# ICs.net
KiCad netlist of a schematic drawn in Altium Designer
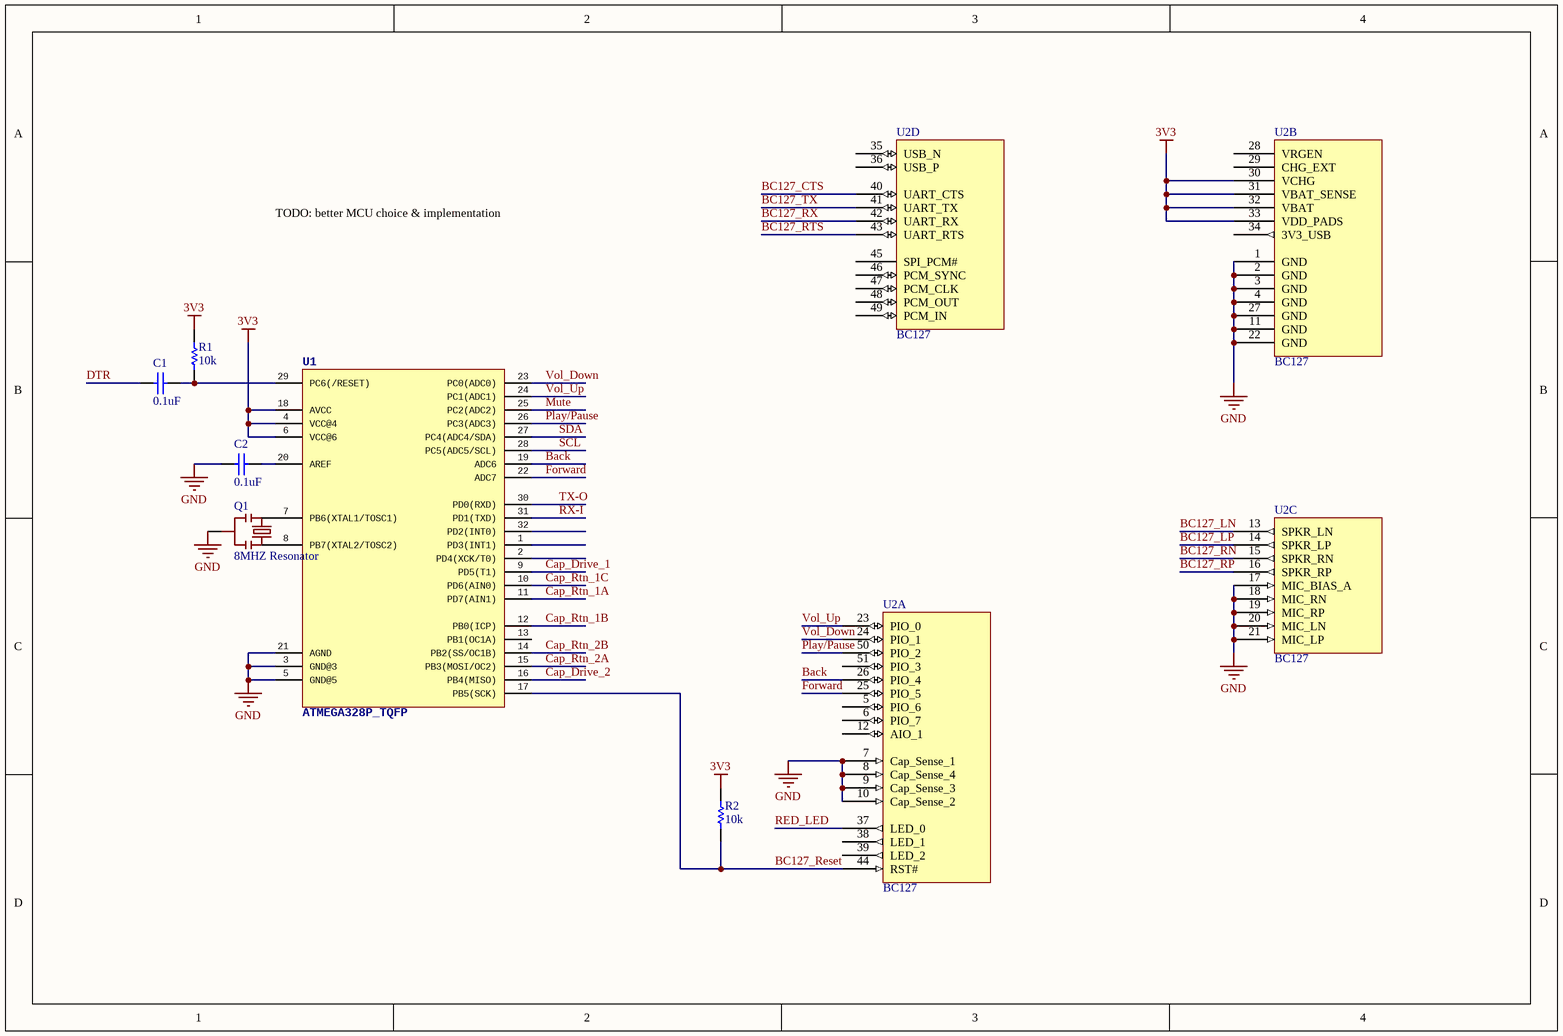
[diagram p0: ICs.SchDoc]

(export (version "E")
  (design (tool "Eeschema 10.0.6"))
  (components
    (comp (ref "C1")
      (value "0.1uF")
      (footprint "CAPC1608X09N")
      (fields
        (field (name "DIGIKEY PART NUMBER") "490-3285-1-ND")
        (field (name "VOLTAGE") "100V")
        (field (name "TOLERANCE") "10%")
      )
      (libsource (lib "Speaker Library") (part "CAP CER 0.1uF 0603"))
    )
    (comp (ref "C2")
      (value "0.1uF")
      (footprint "CAPC1608X09N")
      (fields
        (field (name "DIGIKEY PART NUMBER") "490-3285-1-ND")
        (field (name "VOLTAGE") "100V")
        (field (name "TOLERANCE") "10%")
      )
      (libsource (lib "Speaker Library") (part "CAP CER 0.1uF 0603"))
    )
    (comp (ref "Q1")
      (value "8MHZ Resonator")
      (footprint "MURATA CSTCE8M00G52Z-R0")
      (fields (field (name "DIGIKEY PART NUMBER") "490-5995-1-ND"))
      (libsource (lib "Speaker Library") (part "RESONATOR 8MHZ"))
    )
    (comp (ref "R1")
      (value "10k")
      (footprint "RESC1608X06N")
      (fields
        (field (name "TOLERANCE") "1%")
        (field (name "POWER") "0.1W")
        (field (name "MANUFACTURER") "Yageo")
      )
      (libsource (lib "Speaker Library") (part "RES 10K 0603"))
    )
    (comp (ref "R2")
      (value "10k")
      (footprint "RESC1608X06N")
      (fields
        (field (name "TOLERANCE") "1%")
        (field (name "POWER") "0.1W")
        (field (name "MANUFACTURER") "Yageo")
      )
      (libsource (lib "Speaker Library") (part "RES 10K 0603"))
    )
    (comp (ref "U1")
      (value "ATMEGA328P_TQFP")
      (footprint "TQFP32-08")
      (fields (field (name "DIGIKEY PART NUMBER") "ATMEGA328P-AURCT-ND"))
      (libsource (lib "Speaker Library") (part "ATMEGA328P_TQFP"))
    )
    (comp (ref "U2") (value "BC127") (footprint "BC127 - No Keepout") (libsource (lib "") (part "BC127_1")))
  )
  (nets
    (net (code "1") (name "/BC127_CTS") (class "Default")
      (node (ref "U2") (pin "40") (pinfunction "UART_CTS_40") (pintype "bidirectional"))
    )
    (net (code "2") (name "/BC127_LN") (class "Default")
      (node (ref "U2") (pin "13") (pinfunction "SPKR_LN_13") (pintype "output"))
    )
    (net (code "3") (name "/BC127_LP") (class "Default")
      (node (ref "U2") (pin "14") (pinfunction "SPKR_LP_14") (pintype "output"))
    )
    (net (code "4") (name "/BC127_RN") (class "Default")
      (node (ref "U2") (pin "15") (pinfunction "SPKR_RN_15") (pintype "output"))
    )
    (net (code "5") (name "/BC127_RP") (class "Default")
      (node (ref "U2") (pin "16") (pinfunction "SPKR_RP_16") (pintype "output"))
    )
    (net (code "6") (name "/BC127_RTS") (class "Default")
      (node (ref "U2") (pin "43") (pinfunction "UART_RTS_43") (pintype "bidirectional"))
    )
    (net (code "7") (name "/BC127_RX") (class "Default")
      (node (ref "U2") (pin "42") (pinfunction "UART_RX_42") (pintype "bidirectional"))
    )
    (net (code "8") (name "/BC127_Reset") (class "Default")
      (node (ref "R2") (pin "1") (pinfunction "1_1") (pintype "passive"))
      (node (ref "U1") (pin "17") (pinfunction "PB5(SCK)_17") (pintype "passive"))
      (node (ref "U2") (pin "44") (pinfunction "RST#_44") (pintype "input"))
    )
    (net (code "9") (name "/BC127_TX") (class "Default")
      (node (ref "U2") (pin "41") (pinfunction "UART_TX_41") (pintype "bidirectional"))
    )
    (net (code "10") (name "/Back") (class "Default")
      (node (ref "U1") (pin "19") (pinfunction "ADC6_19") (pintype "passive"))
      (node (ref "U2") (pin "26") (pinfunction "PIO_4_26") (pintype "bidirectional"))
    )
    (net (code "11") (name "/Cap_Drive_1") (class "Default")
      (node (ref "U1") (pin "9") (pinfunction "PD5(T1)_9") (pintype "passive"))
    )
    (net (code "12") (name "/Cap_Drive_2") (class "Default")
      (node (ref "U1") (pin "16") (pinfunction "PB4(MISO)_16") (pintype "passive"))
    )
    (net (code "13") (name "/Cap_Rtn_1A") (class "Default")
      (node (ref "U1") (pin "11") (pinfunction "PD7(AIN1)_11") (pintype "passive"))
    )
    (net (code "14") (name "/Cap_Rtn_1B") (class "Default")
      (node (ref "U1") (pin "12") (pinfunction "PB0(ICP)_12") (pintype "passive"))
    )
    (net (code "15") (name "/Cap_Rtn_1C") (class "Default")
      (node (ref "U1") (pin "10") (pinfunction "PD6(AIN0)_10") (pintype "passive"))
    )
    (net (code "16") (name "/Cap_Rtn_2A") (class "Default")
      (node (ref "U1") (pin "15") (pinfunction "PB3(MOSI/OC2)_15") (pintype "passive"))
    )
    (net (code "17") (name "/Cap_Rtn_2B") (class "Default")
      (node (ref "U1") (pin "14") (pinfunction "PB2(SS/OC1B)_14") (pintype "passive"))
    )
    (net (code "18") (name "/DTR") (class "Default")
      (node (ref "C1") (pin "1") (pinfunction "1_1") (pintype "passive"))
    )
    (net (code "19") (name "/Forward") (class "Default")
      (node (ref "U1") (pin "22") (pinfunction "ADC7_22") (pintype "passive"))
      (node (ref "U2") (pin "25") (pinfunction "PIO_5_25") (pintype "bidirectional"))
    )
    (net (code "20") (name "/Mute") (class "Default")
      (node (ref "U1") (pin "25") (pinfunction "PC2(ADC2)_25") (pintype "passive"))
    )
    (net (code "21") (name "/Play{slash}Pause") (class "Default")
      (node (ref "U1") (pin "26") (pinfunction "PC3(ADC3)_26") (pintype "passive"))
      (node (ref "U2") (pin "50") (pinfunction "PIO_2_50") (pintype "bidirectional"))
    )
    (net (code "22") (name "/RED_LED") (class "Default")
      (node (ref "U2") (pin "37") (pinfunction "LED_0_37") (pintype "output"))
    )
    (net (code "23") (name "/RX-I") (class "Default")
      (node (ref "U1") (pin "31") (pinfunction "PD1(TXD)_31") (pintype "passive"))
    )
    (net (code "24") (name "/SCL") (class "Default")
      (node (ref "U1") (pin "28") (pinfunction "PC5(ADC5/SCL)_28") (pintype "passive"))
    )
    (net (code "25") (name "/SDA") (class "Default")
      (node (ref "U1") (pin "27") (pinfunction "PC4(ADC4/SDA)_27") (pintype "passive"))
    )
    (net (code "26") (name "/TX-O") (class "Default")
      (node (ref "U1") (pin "30") (pinfunction "PD0(RXD)_30") (pintype "passive"))
    )
    (net (code "27") (name "/Vol_Down") (class "Default")
      (node (ref "U1") (pin "23") (pinfunction "PC0(ADC0)_23") (pintype "passive"))
      (node (ref "U2") (pin "24") (pinfunction "PIO_1_24") (pintype "bidirectional"))
    )
    (net (code "28") (name "/Vol_Up") (class "Default")
      (node (ref "U1") (pin "24") (pinfunction "PC1(ADC1)_24") (pintype "passive"))
      (node (ref "U2") (pin "23") (pinfunction "PIO_0_23") (pintype "bidirectional"))
    )
    (net (code "29") (name "3V3") (class "Default")
      (node (ref "R1") (pin "2") (pinfunction "2_2") (pintype "passive"))
      (node (ref "R2") (pin "2") (pinfunction "2_2") (pintype "passive"))
      (node (ref "U1") (pin "18") (pinfunction "AVCC_18") (pintype "passive"))
      (node (ref "U1") (pin "4") (pinfunction "VCC@4_4") (pintype "power_in"))
      (node (ref "U1") (pin "6") (pinfunction "VCC@6_6") (pintype "power_in"))
      (node (ref "U2") (pin "30") (pinfunction "VCHG_30") (pintype "passive"))
      (node (ref "U2") (pin "31") (pinfunction "VBAT_SENSE_31") (pintype "passive"))
      (node (ref "U2") (pin "32") (pinfunction "VBAT_32") (pintype "passive"))
      (node (ref "U2") (pin "33") (pinfunction "VDD_PADS_33") (pintype "power_in"))
    )
    (net (code "30") (name "GND") (class "Default")
      (node (ref "C2") (pin "1") (pinfunction "1_1") (pintype "passive"))
      (node (ref "Q1") (pin "2") (pinfunction "GND_2") (pintype "passive"))
      (node (ref "U1") (pin "21") (pinfunction "AGND_21") (pintype "power_in"))
      (node (ref "U1") (pin "3") (pinfunction "GND@3_3") (pintype "power_in"))
      (node (ref "U1") (pin "5") (pinfunction "GND@5_5") (pintype "power_in"))
      (node (ref "U2") (pin "1") (pinfunction "GND_1") (pintype "power_in"))
      (node (ref "U2") (pin "10") (pinfunction "Cap_Sense_2_10") (pintype "input"))
      (node (ref "U2") (pin "11") (pinfunction "GND_11") (pintype "power_in"))
      (node (ref "U2") (pin "17") (pinfunction "MIC_BIAS_A_17") (pintype "input"))
      (node (ref "U2") (pin "18") (pinfunction "MIC_RN_18") (pintype "input"))
      (node (ref "U2") (pin "19") (pinfunction "MIC_RP_19") (pintype "input"))
      (node (ref "U2") (pin "2") (pinfunction "GND_2") (pintype "power_in"))
      (node (ref "U2") (pin "20") (pinfunction "MIC_LN_20") (pintype "input"))
      (node (ref "U2") (pin "21") (pinfunction "MIC_LP_21") (pintype "input"))
      (node (ref "U2") (pin "22") (pinfunction "GND_22") (pintype "power_in"))
      (node (ref "U2") (pin "27") (pinfunction "GND_27") (pintype "power_in"))
      (node (ref "U2") (pin "3") (pinfunction "GND_3") (pintype "power_in"))
      (node (ref "U2") (pin "4") (pinfunction "GND_4") (pintype "power_in"))
      (node (ref "U2") (pin "7") (pinfunction "Cap_Sense_1_7") (pintype "input"))
      (node (ref "U2") (pin "8") (pinfunction "Cap_Sense_4_8") (pintype "input"))
      (node (ref "U2") (pin "9") (pinfunction "Cap_Sense_3_9") (pintype "input"))
    )
    (net (code "31") (name "Net-(U1-AREF)") (class "Default")
      (node (ref "C2") (pin "2") (pinfunction "2_2") (pintype "passive"))
      (node (ref "U1") (pin "20") (pinfunction "AREF_20") (pintype "passive"))
    )
    (net (code "32") (name "Net-(U1-PB6(XTAL1{slash}TOSC1))") (class "Default")
      (node (ref "Q1") (pin "1") (pinfunction "1_1") (pintype "passive"))
      (node (ref "U1") (pin "7") (pinfunction "PB6(XTAL1/TOSC1)_7") (pintype "passive"))
    )
    (net (code "33") (name "Net-(U1-PB7(XTAL2{slash}TOSC2))") (class "Default")
      (node (ref "Q1") (pin "3") (pinfunction "3_3") (pintype "passive"))
      (node (ref "U1") (pin "8") (pinfunction "PB7(XTAL2/TOSC2)_8") (pintype "passive"))
    )
    (net (code "34") (name "Net-(U1-PC6({slash}RESET))") (class "Default")
      (node (ref "C1") (pin "2") (pinfunction "2_2") (pintype "passive"))
      (node (ref "R1") (pin "1") (pinfunction "1_1") (pintype "passive"))
      (node (ref "U1") (pin "29") (pinfunction "PC6(/RESET)_29") (pintype "passive"))
    )
    (net (code "35") (name "unconnected-(U1-PB1(OC1A)-Pad13)") (class "Default")
      (node (ref "U1") (pin "13") (pinfunction "PB1(OC1A)_13") (pintype "passive"))
    )
    (net (code "36") (name "unconnected-(U1-PD2(INT0)-Pad32)") (class "Default")
      (node (ref "U1") (pin "32") (pinfunction "PD2(INT0)_32") (pintype "passive"))
    )
    (net (code "37") (name "unconnected-(U1-PD3(INT1)-Pad1)") (class "Default")
      (node (ref "U1") (pin "1") (pinfunction "PD3(INT1)_1") (pintype "passive"))
    )
    (net (code "38") (name "unconnected-(U1-PD4(XCK{slash}T0)-Pad2)") (class "Default")
      (node (ref "U1") (pin "2") (pinfunction "PD4(XCK/T0)_2") (pintype "passive"))
    )
    (net (code "39") (name "unconnected-(U2A-AIO_1-Pad12)") (class "Default")
      (node (ref "U2") (pin "12") (pinfunction "AIO_1_12") (pintype "bidirectional"))
    )
    (net (code "40") (name "unconnected-(U2A-LED_1-Pad38)") (class "Default")
      (node (ref "U2") (pin "38") (pinfunction "LED_1_38") (pintype "output"))
    )
    (net (code "41") (name "unconnected-(U2A-LED_2-Pad39)") (class "Default")
      (node (ref "U2") (pin "39") (pinfunction "LED_2_39") (pintype "output"))
    )
    (net (code "42") (name "unconnected-(U2A-PIO_3-Pad51)") (class "Default")
      (node (ref "U2") (pin "51") (pinfunction "PIO_3_51") (pintype "bidirectional"))
    )
    (net (code "43") (name "unconnected-(U2A-PIO_6-Pad5)") (class "Default")
      (node (ref "U2") (pin "5") (pinfunction "PIO_6_5") (pintype "bidirectional"))
    )
    (net (code "44") (name "unconnected-(U2A-PIO_7-Pad6)") (class "Default")
      (node (ref "U2") (pin "6") (pinfunction "PIO_7_6") (pintype "bidirectional"))
    )
    (net (code "45") (name "unconnected-(U2B-3V3_USB-Pad34)") (class "Default")
      (node (ref "U2") (pin "34") (pinfunction "3V3_USB_34") (pintype "output"))
    )
    (net (code "46") (name "unconnected-(U2B-CHG_EXT-Pad29)") (class "Default")
      (node (ref "U2") (pin "29") (pinfunction "CHG_EXT_29") (pintype "passive"))
    )
    (net (code "47") (name "unconnected-(U2B-VRGEN-Pad28)") (class "Default")
      (node (ref "U2") (pin "28") (pinfunction "VRGEN_28") (pintype "passive"))
    )
    (net (code "48") (name "unconnected-(U2D-PCM_CLK-Pad47)") (class "Default")
      (node (ref "U2") (pin "47") (pinfunction "PCM_CLK_47") (pintype "bidirectional"))
    )
    (net (code "49") (name "unconnected-(U2D-PCM_IN-Pad49)") (class "Default")
      (node (ref "U2") (pin "49") (pinfunction "PCM_IN_49") (pintype "bidirectional"))
    )
    (net (code "50") (name "unconnected-(U2D-PCM_OUT-Pad48)") (class "Default")
      (node (ref "U2") (pin "48") (pinfunction "PCM_OUT_48") (pintype "bidirectional"))
    )
    (net (code "51") (name "unconnected-(U2D-PCM_SYNC-Pad46)") (class "Default")
      (node (ref "U2") (pin "46") (pinfunction "PCM_SYNC_46") (pintype "bidirectional"))
    )
    (net (code "52") (name "unconnected-(U2D-SPI_PCM#-Pad45)") (class "Default")
      (node (ref "U2") (pin "45") (pinfunction "SPI_PCM#_45") (pintype "passive"))
    )
    (net (code "53") (name "unconnected-(U2D-USB_N-Pad35)") (class "Default")
      (node (ref "U2") (pin "35") (pinfunction "USB_N_35") (pintype "bidirectional"))
    )
    (net (code "54") (name "unconnected-(U2D-USB_P-Pad36)") (class "Default")
      (node (ref "U2") (pin "36") (pinfunction "USB_P_36") (pintype "bidirectional"))
    )
  )
)
